# SCH_PCB-card_2024-10-28.net
KiCad netlist of a schematic drawn in EasyEDA
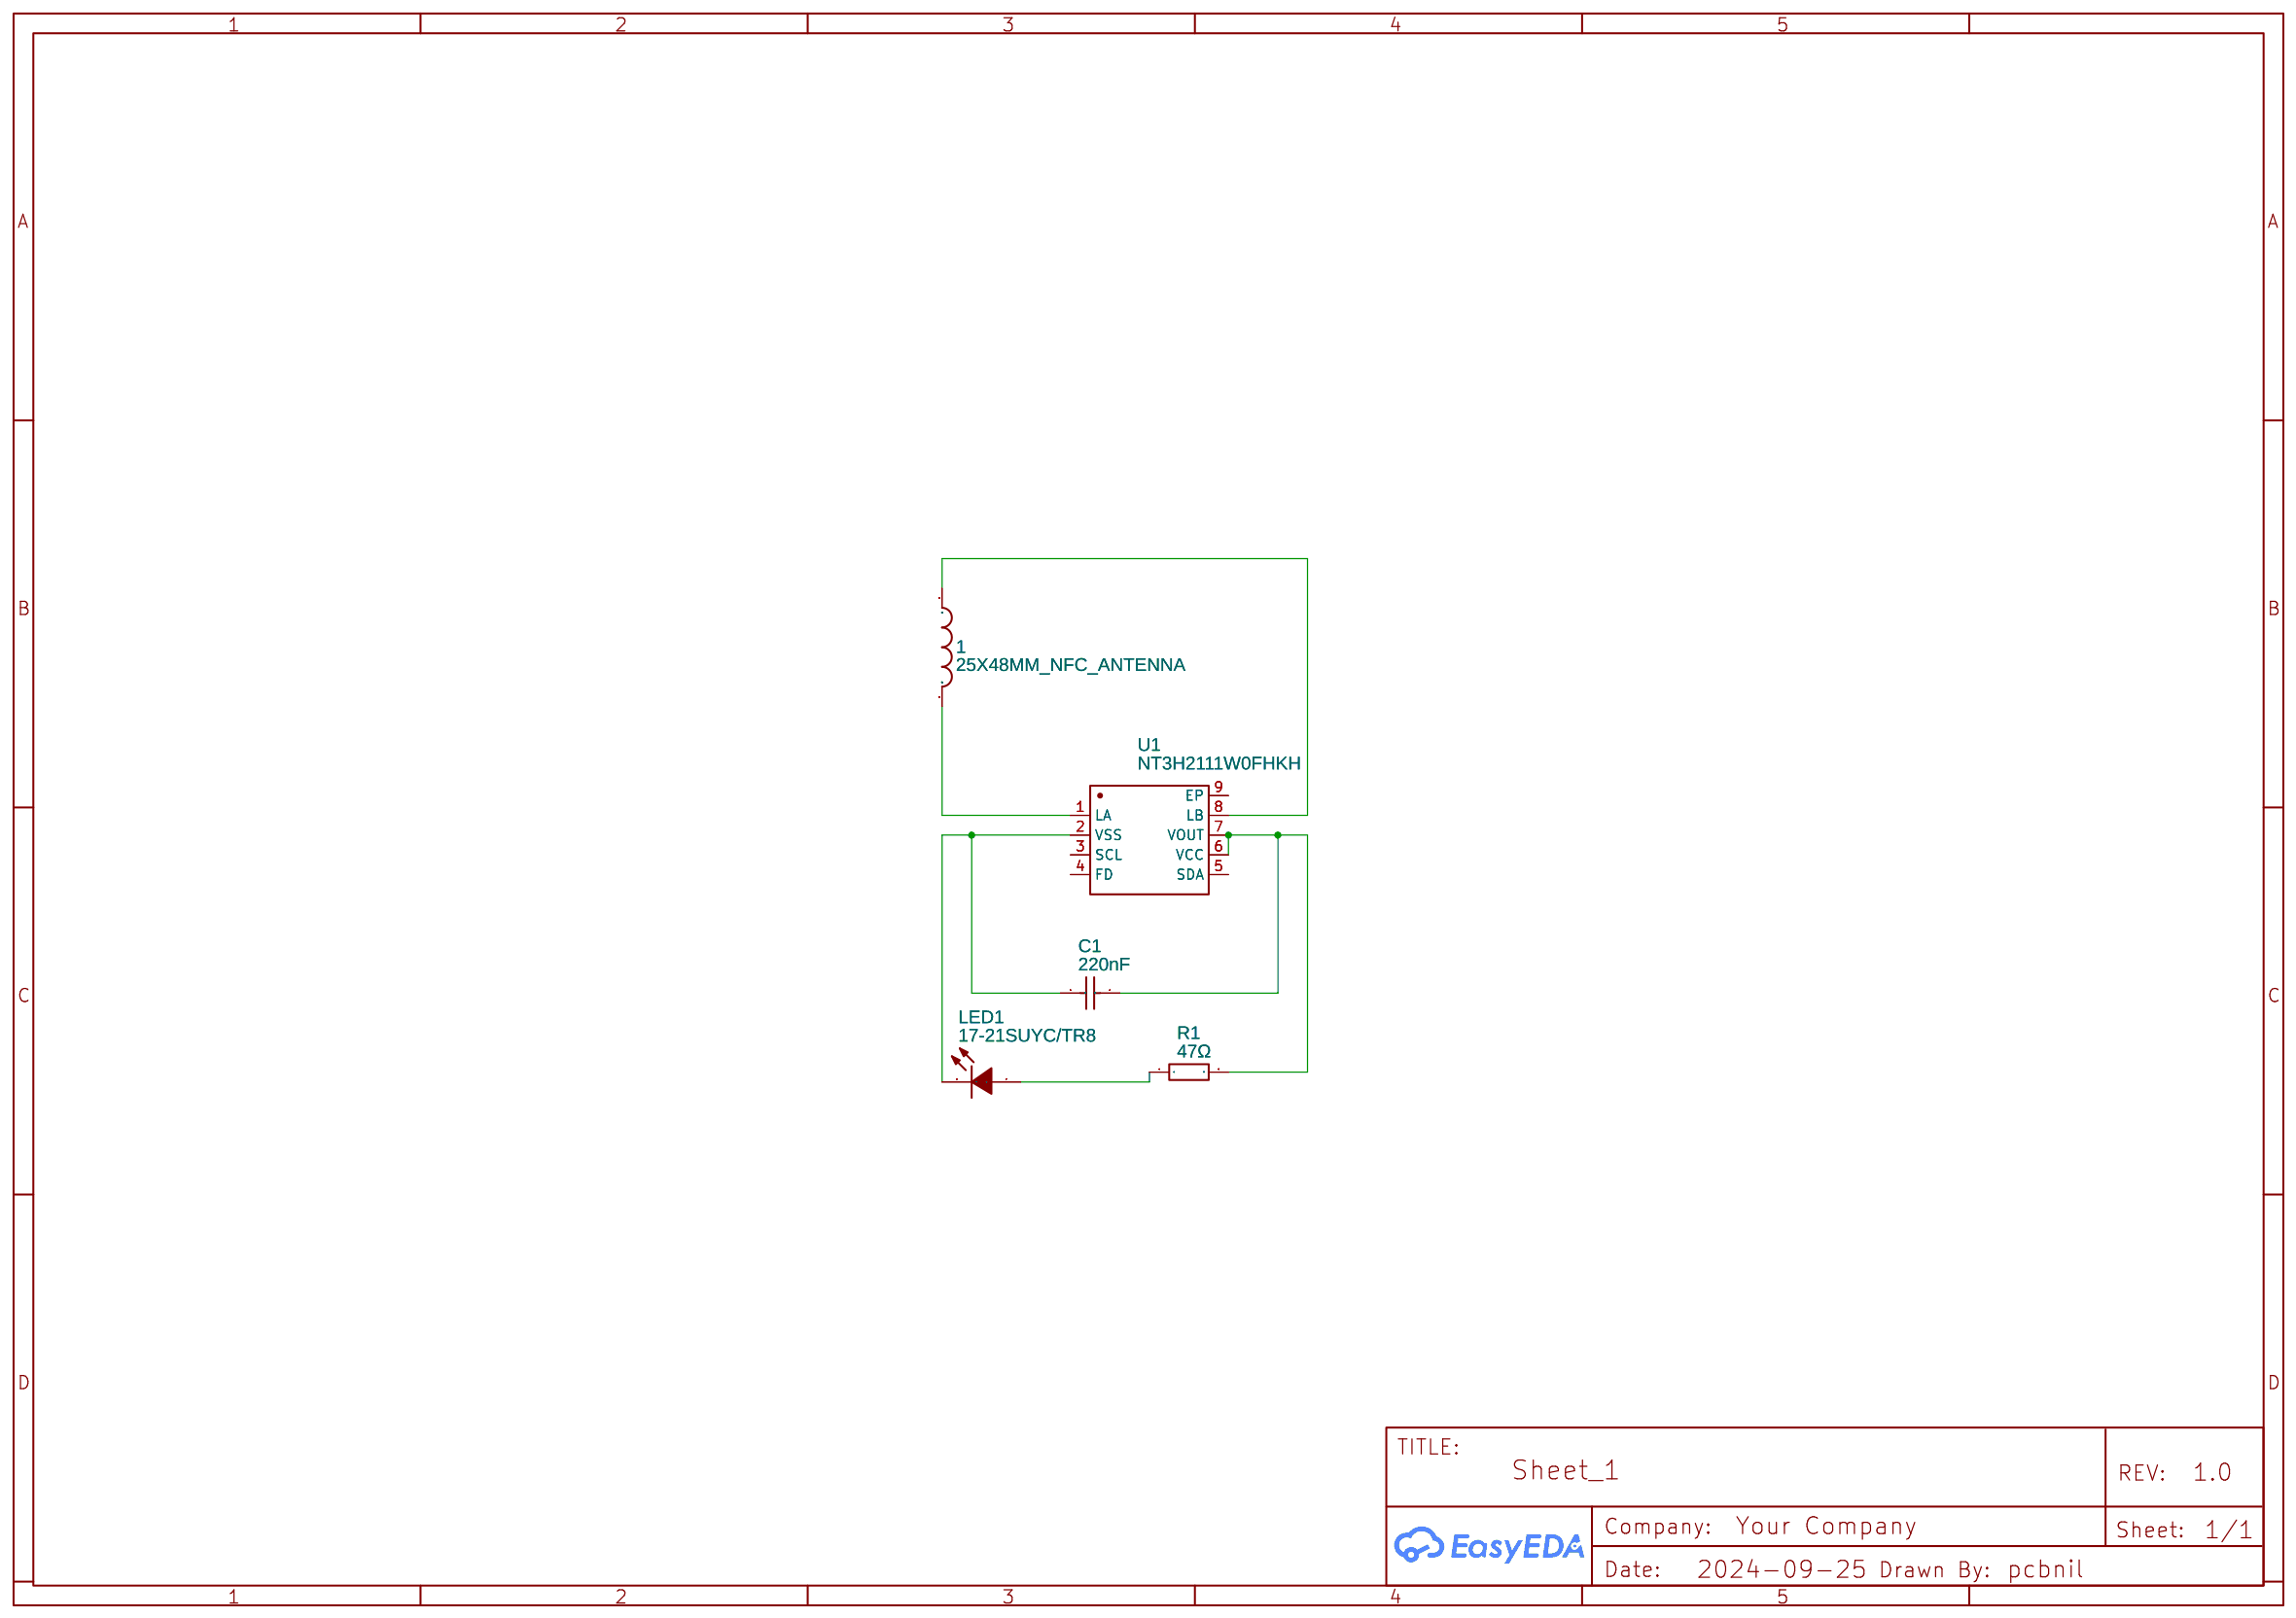
[diagram p0: schematic sheet]

(export (version "E")
  (design (tool "Eeschema 10.0.6"))
  (components
    (comp (ref "1") (value "25X48MM_NFC_ANTENNA") (libsource (lib "") (part "25X48MM_NFC_ANTENNA")))
    (comp (ref "C1")
      (value "220nF")
      (fields
        (field (name "Manufacturer Part") "CL10B224KA8NNNC")
        (field (name "Manufacturer") "SAMSUNG(三星)")
      )
      (libsource (lib "") (part "CL10B224KA8NNNC"))
    )
    (comp (ref "LED1")
      (value "17-21SUYC/TR8")
      (fields (field (name "Manufacturer Part") "KT-0805黄灯") (field (name "Manufacturer") "KENTO"))
      (libsource (lib "") (part "17-21SUYC/TR8"))
    )
    (comp (ref "R1")
      (value "47Ω")
      (fields
        (field (name "Manufacturer Part") "0603WAF470JT5E")
        (field (name "Manufacturer") "UNI-ROYAL(厚声)")
      )
      (libsource (lib "") (part "0603WAF470JT5E"))
    )
    (comp (ref "U1")
      (value "NT3H2111W0FHKH")
      (fields (field (name "Manufacturer") "NXP(恩智浦)"))
      (libsource (lib "") (part "NT3H2111W0FHKH"))
    )
  )
  (nets
    (net (code "1") (name "Net-(LED1-+)") (class "Default")
      (node (ref "LED1") (pin "1") (pinfunction "+_1") (pintype "unspecified"))
      (node (ref "R1") (pin "1") (pinfunction "1_1") (pintype "input"))
    )
    (net (code "2") (name "Net-(LED1--)") (class "Default")
      (node (ref "C1") (pin "1") (pinfunction "1_1") (pintype "input"))
      (node (ref "LED1") (pin "2") (pinfunction "-_2") (pintype "unspecified"))
      (node (ref "U1") (pin "2") (pinfunction "VSS_2") (pintype "unspecified"))
    )
    (net (code "3") (name "Net-(U1-LA)") (class "Default")
      (node (ref "1") (pin "P$2") (pinfunction "P$2_P$2") (pintype "bidirectional"))
      (node (ref "U1") (pin "1") (pinfunction "LA_1") (pintype "unspecified"))
    )
    (net (code "4") (name "Net-(U1-LB)") (class "Default")
      (node (ref "1") (pin "P$1") (pinfunction "P$1_P$1") (pintype "bidirectional"))
      (node (ref "U1") (pin "8") (pinfunction "LB_8") (pintype "unspecified"))
    )
    (net (code "5") (name "Net-(U1-VCC)") (class "Default")
      (node (ref "C1") (pin "2") (pinfunction "2_2") (pintype "input"))
      (node (ref "R1") (pin "2") (pinfunction "2_2") (pintype "input"))
      (node (ref "U1") (pin "6") (pinfunction "VCC_6") (pintype "unspecified"))
      (node (ref "U1") (pin "7") (pinfunction "VOUT_7") (pintype "unspecified"))
    )
    (net (code "6") (name "unconnected-(U1-EP-Pad9)") (class "Default")
      (node (ref "U1") (pin "9") (pinfunction "EP_9") (pintype "unspecified"))
    )
    (net (code "7") (name "unconnected-(U1-FD-Pad4)") (class "Default")
      (node (ref "U1") (pin "4") (pinfunction "FD_4") (pintype "unspecified"))
    )
    (net (code "8") (name "unconnected-(U1-SCL-Pad3)") (class "Default")
      (node (ref "U1") (pin "3") (pinfunction "SCL_3") (pintype "unspecified"))
    )
    (net (code "9") (name "unconnected-(U1-SDA-Pad5)") (class "Default")
      (node (ref "U1") (pin "5") (pinfunction "SDA_5") (pintype "unspecified"))
    )
  )
)
